# RJ45_Breakout.net
KiCad netlist of a schematic drawn in EAGLE
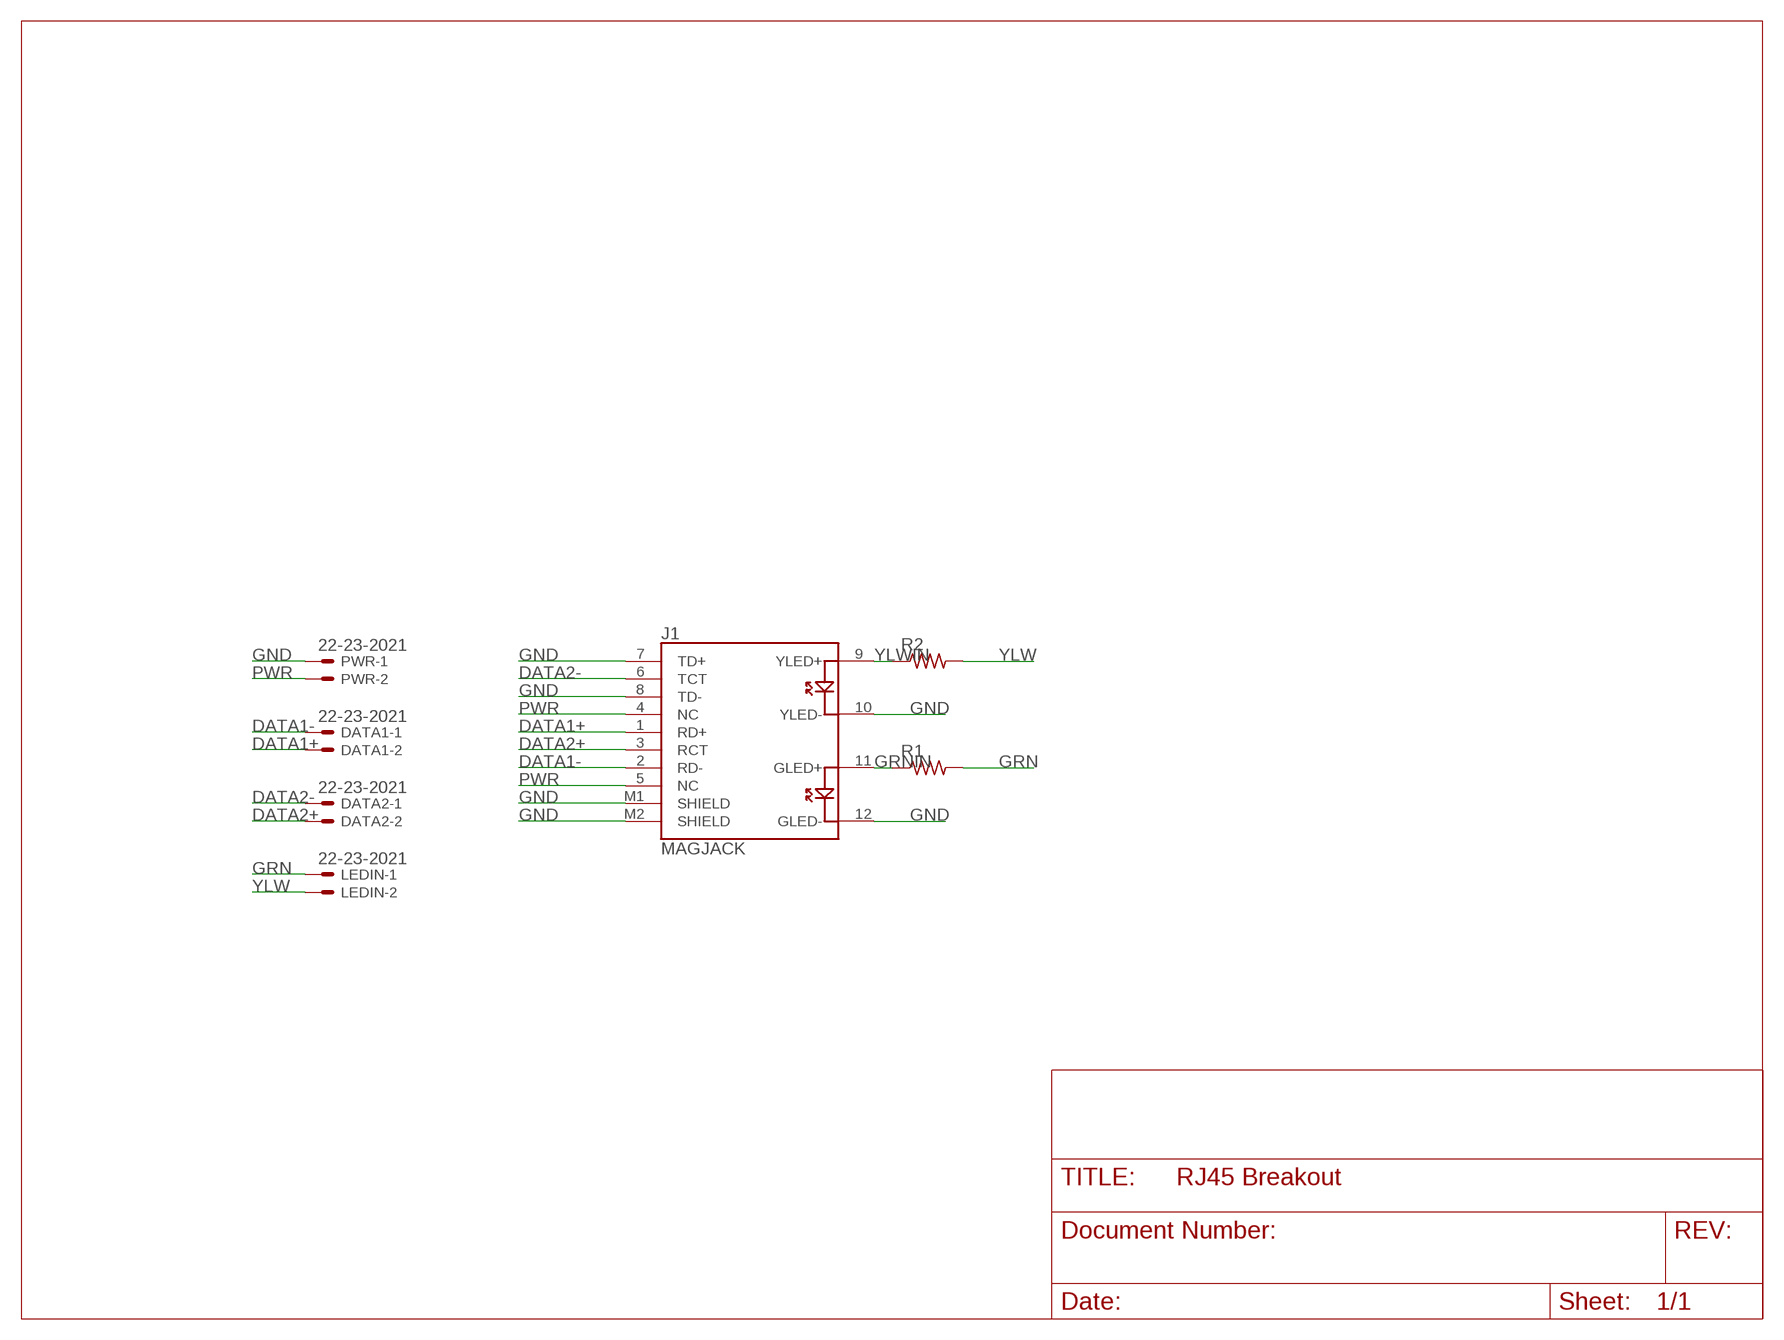
[diagram p0: schematic, sheet 1]

(export (version "E")
  (design (tool "Eeschema 10.0.6"))
  (components
    (comp (ref "DATA1")
      (value "22-23-2021")
      (footprint "eagle-import:22-23-2021")
      (fields (field (name "MF") "MOLEX"))
      (libsource (lib "eagle-import") (part "22-23-2021"))
    )
    (comp (ref "DATA2")
      (value "22-23-2021")
      (footprint "eagle-import:22-23-2021")
      (fields (field (name "MF") "MOLEX"))
      (libsource (lib "eagle-import") (part "22-23-2021"))
    )
    (comp (ref "J1")
      (value "MAGJACK")
      (footprint "eagle-import:MAGJACK")
      (libsource (lib "eagle-import") (part "MAGJACK"))
    )
    (comp (ref "LEDIN")
      (value "22-23-2021")
      (footprint "eagle-import:22-23-2021")
      (fields (field (name "MF") "MOLEX"))
      (libsource (lib "eagle-import") (part "22-23-2021"))
    )
    (comp (ref "PWR")
      (value "22-23-2021")
      (footprint "eagle-import:22-23-2021")
      (fields (field (name "MF") "MOLEX"))
      (libsource (lib "eagle-import") (part "22-23-2021"))
    )
    (comp (ref "R1")
      (value "R-US_0207/10")
      (footprint "eagle-import:0207_10")
      (libsource (lib "eagle-import") (part "R-US_0207/10"))
    )
    (comp (ref "R2")
      (value "R-US_0207/10")
      (footprint "eagle-import:0207_10")
      (libsource (lib "eagle-import") (part "R-US_0207/10"))
    )
  )
  (nets
    (net (code "1") (name "/DATA1+") (class "Default")
      (node (ref "DATA1") (pin "2") (pinfunction "S_2") (pintype "passive"))
      (node (ref "J1") (pin "1") (pinfunction "RD+_1") (pintype "bidirectional"))
    )
    (net (code "2") (name "/DATA1-") (class "Default")
      (node (ref "DATA1") (pin "1") (pinfunction "S_1") (pintype "passive"))
      (node (ref "J1") (pin "2") (pinfunction "RD-_2") (pintype "bidirectional"))
    )
    (net (code "3") (name "/DATA2+") (class "Default")
      (node (ref "DATA2") (pin "2") (pinfunction "S_2") (pintype "passive"))
      (node (ref "J1") (pin "3") (pinfunction "RCT_3") (pintype "bidirectional"))
    )
    (net (code "4") (name "/DATA2-") (class "Default")
      (node (ref "DATA2") (pin "1") (pinfunction "S_1") (pintype "passive"))
      (node (ref "J1") (pin "6") (pinfunction "TCT_6") (pintype "bidirectional"))
    )
    (net (code "5") (name "/GND") (class "Default")
      (node (ref "J1") (pin "10") (pinfunction "YLED-_10") (pintype "bidirectional"))
      (node (ref "J1") (pin "12") (pinfunction "GLED-_12") (pintype "bidirectional"))
      (node (ref "J1") (pin "7") (pinfunction "TD+_7") (pintype "bidirectional"))
      (node (ref "J1") (pin "8") (pinfunction "TD-_8") (pintype "bidirectional"))
      (node (ref "J1") (pin "M1") (pinfunction "SHIELD_M1") (pintype "bidirectional"))
      (node (ref "J1") (pin "M2") (pinfunction "SHIELD_M2") (pintype "bidirectional"))
      (node (ref "PWR") (pin "1") (pinfunction "S_1") (pintype "passive"))
    )
    (net (code "6") (name "/GRN") (class "Default")
      (node (ref "LEDIN") (pin "1") (pinfunction "S_1") (pintype "passive"))
      (node (ref "R1") (pin "2") (pinfunction "2_2") (pintype "passive"))
    )
    (net (code "7") (name "/GRNIN") (class "Default")
      (node (ref "J1") (pin "11") (pinfunction "GLED+_11") (pintype "bidirectional"))
      (node (ref "R1") (pin "1") (pinfunction "1_1") (pintype "passive"))
    )
    (net (code "8") (name "/PWR") (class "Default")
      (node (ref "J1") (pin "4") (pinfunction "NC_4") (pintype "bidirectional"))
      (node (ref "J1") (pin "5") (pinfunction "NC_5") (pintype "bidirectional"))
      (node (ref "PWR") (pin "2") (pinfunction "S_2") (pintype "passive"))
    )
    (net (code "9") (name "/YLW") (class "Default")
      (node (ref "LEDIN") (pin "2") (pinfunction "S_2") (pintype "passive"))
      (node (ref "R2") (pin "2") (pinfunction "2_2") (pintype "passive"))
    )
    (net (code "10") (name "/YLWIN") (class "Default")
      (node (ref "J1") (pin "9") (pinfunction "YLED+_9") (pintype "bidirectional"))
      (node (ref "R2") (pin "1") (pinfunction "1_1") (pintype "passive"))
    )
  )
)
